# Stepper_Motor1.net
KiCad netlist of a schematic drawn in Altium Designer
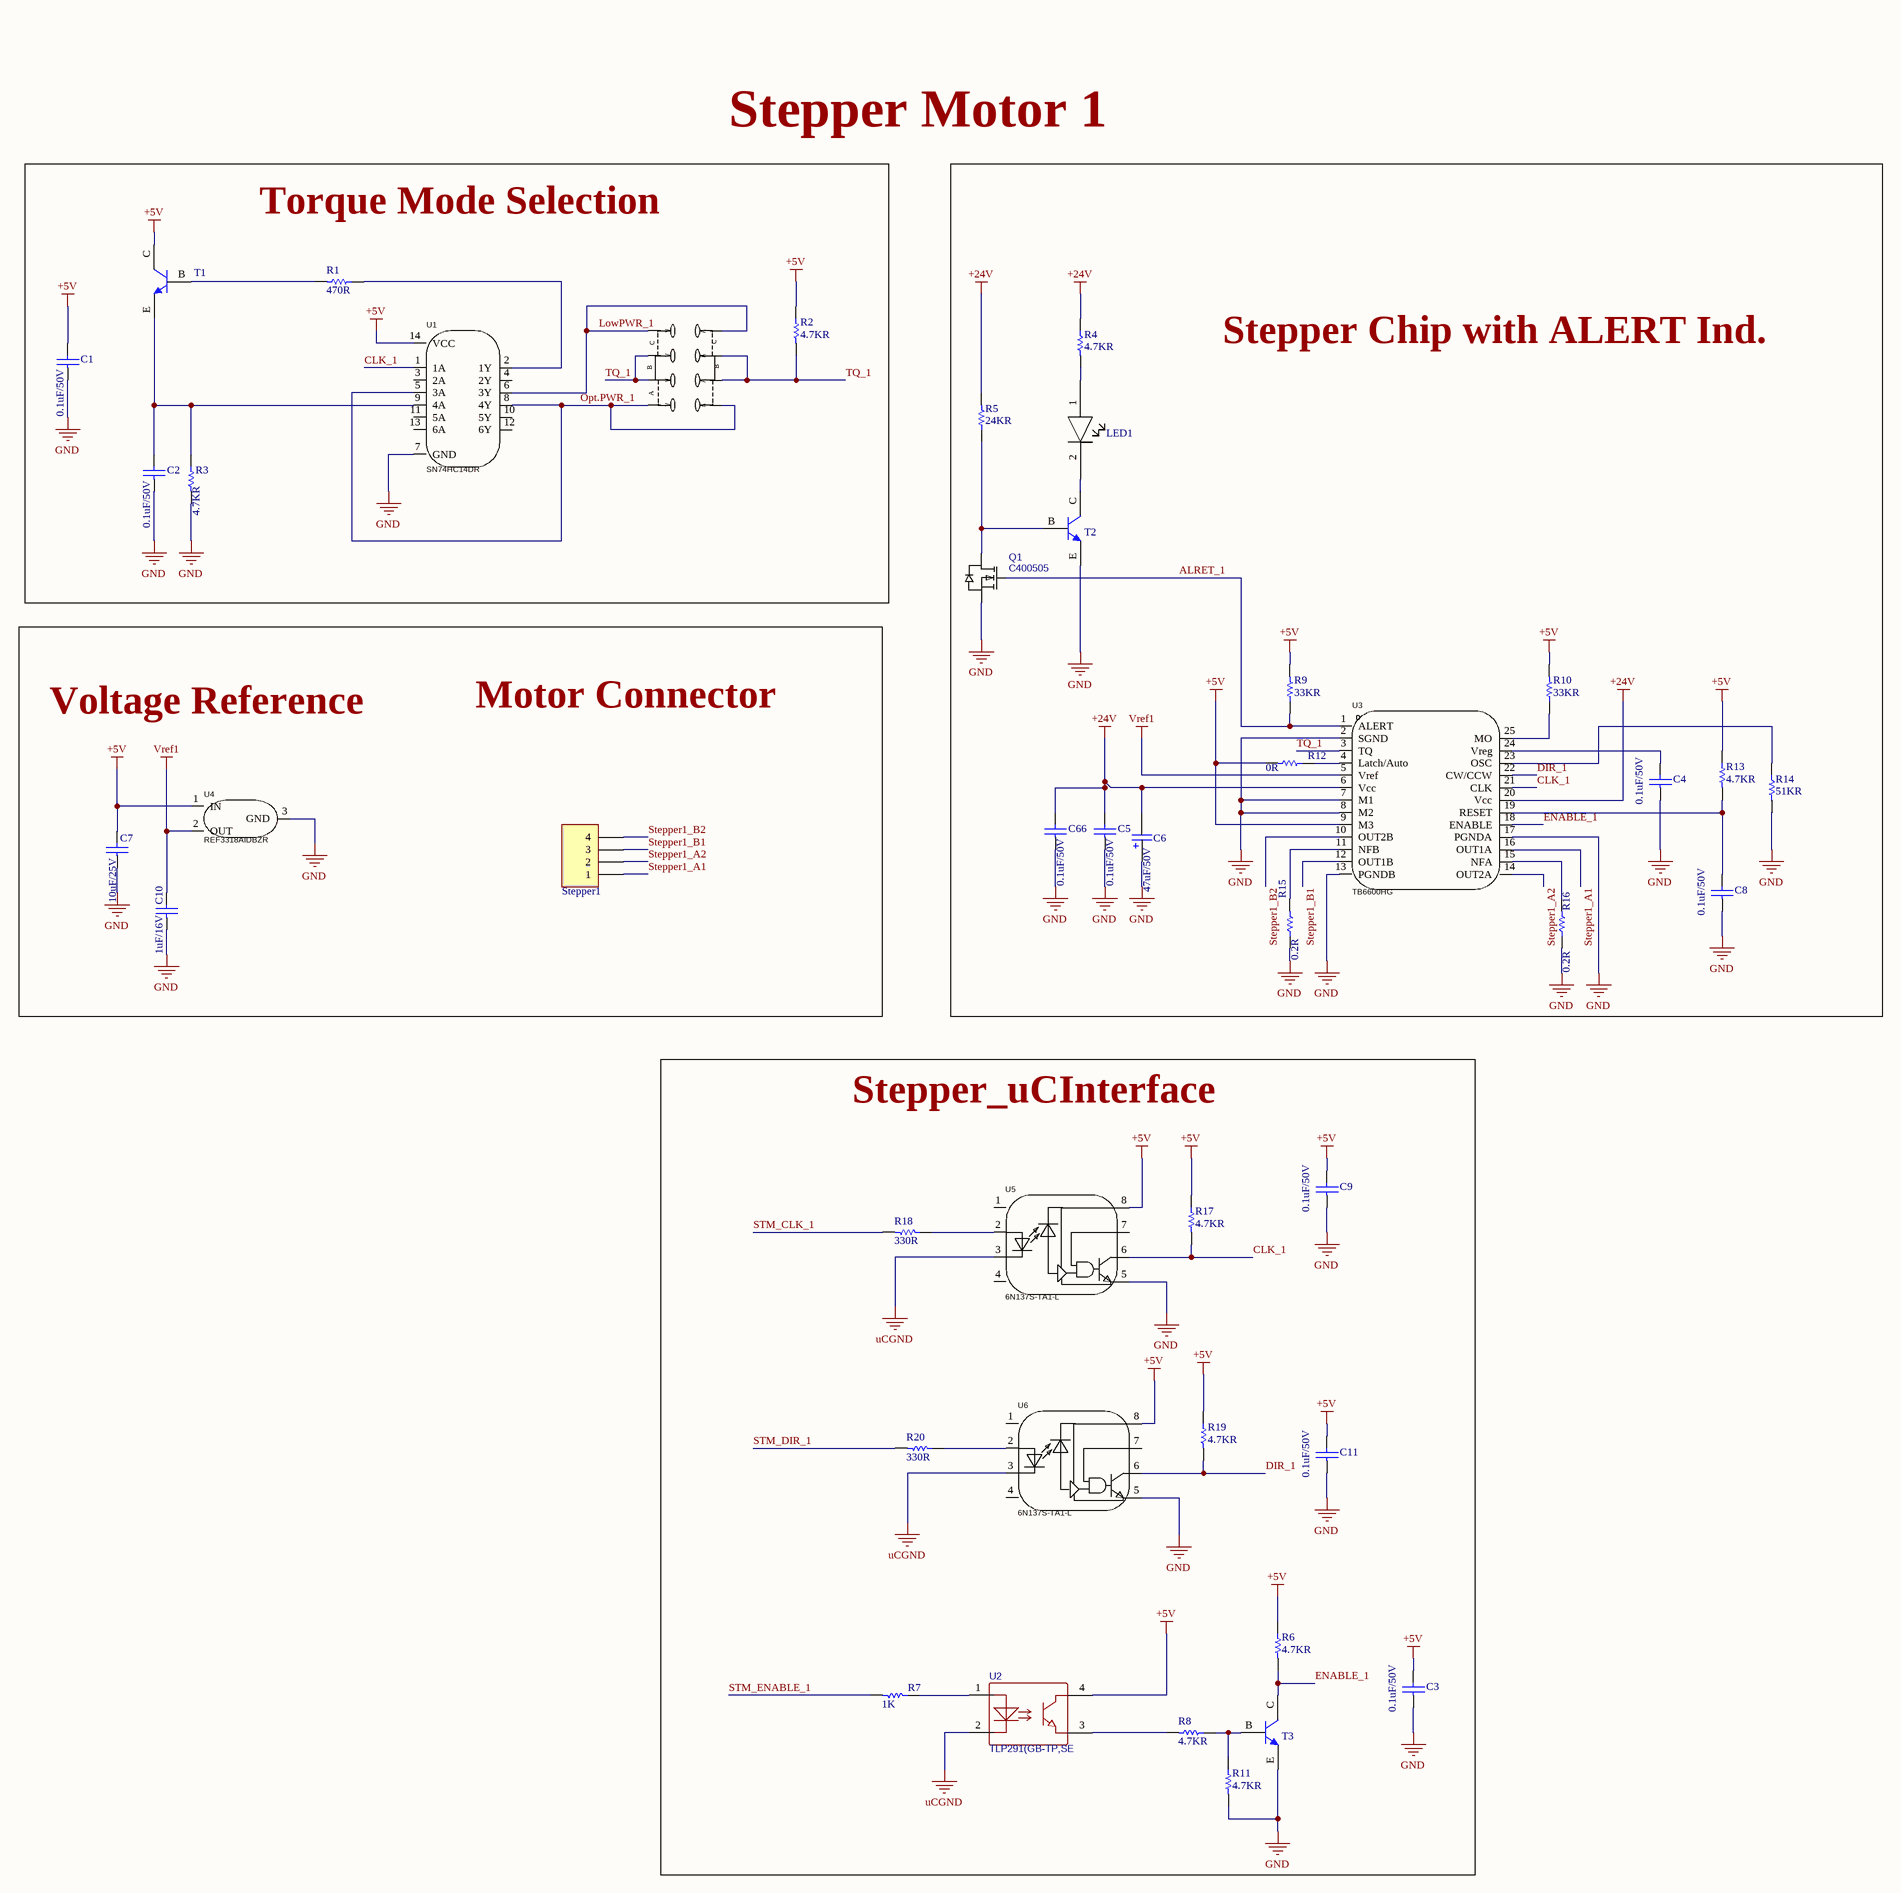
[diagram p0: Stepper Motor1.SchDoc]

(export (version "E")
  (design (tool "Eeschema 10.0.6"))
  (components
    (comp (ref "C1")
      (value "0.1uF/50V")
      (footprint "PCBComponent_1")
      (description "C1591")
      (fields (field (name "CREATED BY") "NourAldin"))
      (libsource (lib "0603 Capacitor") (part "0603 Capacitor"))
    )
    (comp (ref "C2")
      (value "0.1uF/50V")
      (footprint "PCBComponent_1")
      (description "C1591")
      (fields (field (name "CREATED BY") "NourAldin"))
      (libsource (lib "0603 Capacitor") (part "0603 Capacitor"))
    )
    (comp (ref "C3")
      (value "0.1uF/50V")
      (footprint "PCBComponent_1")
      (description "C1591")
      (fields (field (name "CREATED BY") "NourAldin"))
      (libsource (lib "0603 Capacitor") (part "0603 Capacitor"))
    )
    (comp (ref "C4")
      (value "0.1uF/50V")
      (footprint "PCBComponent_1")
      (description "C1591")
      (fields (field (name "CREATED BY") "NourAldin"))
      (libsource (lib "0603 Capacitor") (part "0603 Capacitor"))
    )
    (comp (ref "C5")
      (value "0.1uF/50V")
      (footprint "PCBComponent_1")
      (description "C1591")
      (fields (field (name "CREATED BY") "NourAldin"))
      (libsource (lib "0603 Capacitor") (part "0603 Capacitor"))
    )
    (comp (ref "C6")
      (value "47uF/50V")
      (footprint "CAPLEAD_D6.3mm")
      (description "C45100")
      (fields
        (field (name "MANUFACTURER") "KEMET")
        (field (name "MANUFACTURER PART NUMBER") "A759EQ475M2AAAE160")
      )
      (libsource (lib "GlobalLib") (part "A759EQ475M2AAAE160"))
    )
    (comp (ref "C7")
      (value "10uF/25V")
      (footprint "PCBComponent_1")
      (description "C96446")
      (fields (field (name "CREATED BY") "NourAldin"))
      (libsource (lib "0603 Capacitor") (part "0603 Capacitor"))
    )
    (comp (ref "C8")
      (value "0.1uF/50V")
      (footprint "PCBComponent_1")
      (description "C1591")
      (fields (field (name "CREATED BY") "NourAldin"))
      (libsource (lib "0603 Capacitor") (part "0603 Capacitor"))
    )
    (comp (ref "C9")
      (value "0.1uF/50V")
      (footprint "PCBComponent_1")
      (description "C1591")
      (fields (field (name "CREATED BY") "NourAldin"))
      (libsource (lib "0603 Capacitor") (part "0603 Capacitor"))
    )
    (comp (ref "C10")
      (value "1uF/16V")
      (footprint "PCBComponent_1")
      (description "C1592")
      (fields (field (name "CREATED BY") "NourAldin"))
      (libsource (lib "0603 Capacitor") (part "0603 Capacitor"))
    )
    (comp (ref "C11")
      (value "0.1uF/50V")
      (footprint "PCBComponent_1")
      (description "C1591")
      (fields (field (name "CREATED BY") "NourAldin"))
      (libsource (lib "0603 Capacitor") (part "0603 Capacitor"))
    )
    (comp (ref "C66")
      (value "0.1uF/50V")
      (footprint "PCBComponent_1")
      (description "C1591")
      (fields (field (name "CREATED BY") "NourAldin"))
      (libsource (lib "0603 Capacitor") (part "0603 Capacitor"))
    )
    (comp (ref "LED1")
      (value "1206 LED")
      (footprint "1206 LED")
      (description "C434438")
      (fields (field (name "CREATED BY") "NourAldin"))
      (libsource (lib "1206 LED") (part "1206 LED"))
    )
    (comp (ref "Q1")
      (value "C400505")
      (footprint "SOT-23-3_L2.9-W1.3-P1.90-LS2.4-BR")
      (fields
        (field (name "MANUFACTURER") "YANGJIE(扬杰)")
        (field (name "MANUFACTURER PART") "BSS138")
        (field (name "CONTRIBUTOR") "LCSC")
      )
      (libsource (lib "DIVERSE") (part "BSS138_MOSFET"))
    )
    (comp (ref "R1")
      (value "470R")
      (footprint "RESC1608X06N")
      (description "C114669")
      (fields (field (name "CREATED BY") "NourAldin"))
      (libsource (lib "0603 Resistor") (part "0603 Resistor"))
    )
    (comp (ref "R2")
      (value "4.7KR")
      (footprint "R0402")
      (description "C105871")
      (libsource (lib "DIVERSE") (part "0402 Resistor"))
    )
    (comp (ref "R3")
      (value "4.7KR")
      (footprint "R0402")
      (description "C105871")
      (libsource (lib "DIVERSE") (part "0402 Resistor"))
    )
    (comp (ref "R4")
      (value "4.7KR")
      (footprint "R0402")
      (description "C105871")
      (libsource (lib "DIVERSE") (part "0402 Resistor"))
    )
    (comp (ref "R5")
      (value "24KR")
      (footprint "RESC1608X06N")
      (description "C2930081")
      (fields (field (name "CREATED BY") "NourAldin"))
      (libsource (lib "0603 Resistor") (part "0603 Resistor"))
    )
    (comp (ref "R6")
      (value "4.7KR")
      (footprint "R0402")
      (description "C105871")
      (libsource (lib "DIVERSE") (part "0402 Resistor"))
    )
    (comp (ref "R7")
      (value "1K")
      (footprint "R0402")
      (description "C106235")
      (libsource (lib "DIVERSE") (part "0402 Resistor"))
    )
    (comp (ref "R8")
      (value "4.7KR")
      (footprint "R0402")
      (description "C105871")
      (libsource (lib "DIVERSE") (part "0402 Resistor"))
    )
    (comp (ref "R9")
      (value "33KR")
      (footprint "RESC1608X06N")
      (description "C126359")
      (fields (field (name "CREATED BY") "NourAldin"))
      (libsource (lib "0603 Resistor") (part "0603 Resistor"))
    )
    (comp (ref "R10")
      (value "33KR")
      (footprint "RESC1608X06N")
      (description "C126359")
      (fields (field (name "CREATED BY") "NourAldin"))
      (libsource (lib "0603 Resistor") (part "0603 Resistor"))
    )
    (comp (ref "R11")
      (value "4.7KR")
      (footprint "R0402")
      (description "C105871")
      (libsource (lib "DIVERSE") (part "0402 Resistor"))
    )
    (comp (ref "R12")
      (value "0R")
      (footprint "RESC1608X06N")
      (description "C100044")
      (fields (field (name "CREATED BY") "NourAldin"))
      (libsource (lib "0603 Resistor") (part "0603 Resistor"))
    )
    (comp (ref "R13")
      (value "4.7KR")
      (footprint "R0402")
      (description "C105871")
      (libsource (lib "DIVERSE") (part "0402 Resistor"))
    )
    (comp (ref "R14")
      (value "51KR")
      (footprint "R0402")
      (description "C107230")
      (libsource (lib "DIVERSE") (part "0402 Resistor"))
    )
    (comp (ref "R15")
      (value "0.2R")
      (footprint "RESC6431X12N")
      (description "C2903473")
      (fields (field (name "CREATED BY") "NourAldin"))
      (libsource (lib "2512 Resistor") (part "2512 Resistor"))
    )
    (comp (ref "R16")
      (value "0.2R")
      (footprint "RESC6431X12N")
      (description "C2903473")
      (fields (field (name "CREATED BY") "NourAldin"))
      (libsource (lib "2512 Resistor") (part "2512 Resistor"))
    )
    (comp (ref "R17")
      (value "4.7KR")
      (footprint "R0402")
      (description "C105871")
      (libsource (lib "DIVERSE") (part "0402 Resistor"))
    )
    (comp (ref "R18")
      (value "330R")
      (footprint "R0402")
      (description "C105875")
      (libsource (lib "DIVERSE") (part "0402 Resistor"))
    )
    (comp (ref "R19")
      (value "4.7KR")
      (footprint "R0402")
      (description "C105871")
      (libsource (lib "DIVERSE") (part "0402 Resistor"))
    )
    (comp (ref "R20")
      (value "330R")
      (footprint "R0402")
      (description "C105875")
      (libsource (lib "DIVERSE") (part "0402 Resistor"))
    )
    (comp (ref "Stepper1")
      (value "Header 4 Pin Polar")
      (footprint "PCBComponent_1")
      (libsource (lib "Header 4 Pin Polar") (part "Header 4 Pin Polar"))
    )
    (comp (ref "SW1")
      (value "MST23D19G2")
      (footprint "SW-SMD_MST23D19G2")
      (description "C431545")
      (fields (field (name "MANUFACTURER") "SHOU HAN(首韩)"))
      (libsource (lib "LIB") (part "MST23D19G2"))
    )
    (comp (ref "T1")
      (value "MMBT3904 Transistor")
      (footprint "MMBT3904")
      (description "C108429")
      (fields (field (name "CREATED BY") "NourAldin"))
      (libsource (lib "MMBT3904 Transistor") (part "MMBT3904 Transistor"))
    )
    (comp (ref "T2")
      (value "MMBT3904 Transistor")
      (footprint "MMBT3904")
      (description "C108429")
      (fields (field (name "CREATED BY") "NourAldin"))
      (libsource (lib "MMBT3904 Transistor") (part "MMBT3904 Transistor"))
    )
    (comp (ref "T3")
      (value "MMBT3904 Transistor")
      (footprint "MMBT3904")
      (description "C108429")
      (fields (field (name "CREATED BY") "NourAldin"))
      (libsource (lib "MMBT3904 Transistor") (part "MMBT3904 Transistor"))
    )
    (comp (ref "U1")
      (value "SN74HC14DR")
      (footprint "SOIC-14_L8.7-W3.9-P1.27-LS6.0-BL")
      (description "C6820")
      (fields (field (name "MANUFACTURER") "TI(德州仪器)"))
      (libsource (lib "LIB") (part "SN74HC14DR"))
    )
    (comp (ref "U2")
      (value "TLP291(GB-TP,SE")
      (footprint "SOP-4-1.27mm")
      (description "C55144")
      (libsource (lib "CO2_Lib") (part "TLP291(GB-TP,SE(T"))
    )
    (comp (ref "U3")
      (value "TB6600HG")
      (footprint "HZIP25-P-1.00F")
      (description "C66042")
      (fields (field (name "MANUFACTURER") "TOSHIBA(东芝)"))
      (libsource (lib "LIB") (part "TB6600HG"))
    )
    (comp (ref "U4")
      (value "REF3318AIDBZR")
      (footprint "SOT-23-3_L2.9-W1.3-P1.90-LS2.4-BR")
      (description "C115877")
      (fields (field (name "MANUFACTURER") "TI(德州仪器)") (field (name "TOLERANCE") "±0.15%"))
      (libsource (lib "LIB") (part "REF3318AIDBZR"))
    )
    (comp (ref "U5")
      (value "6N137S-TA1-L")
      (footprint "SOP-8_L9.8-W6.6-P2.54-LS10.3-BL")
      (description "C92651")
      (fields (field (name "MANUFACTURER") "LITEON(光宝)"))
      (libsource (lib "LIB") (part "6N137S-TA1-L"))
    )
    (comp (ref "U6")
      (value "6N137S-TA1-L")
      (footprint "SOP-8_L9.8-W6.6-P2.54-LS10.3-BL")
      (description "C92651")
      (fields (field (name "MANUFACTURER") "LITEON(光宝)"))
      (libsource (lib "LIB") (part "6N137S-TA1-L"))
    )
  )
  (nets
    (net (code "1") (name "+5V") (class "Default")
      (node (ref "C1") (pin "2") (pinfunction "2_2") (pintype "passive"))
      (node (ref "C11") (pin "2") (pinfunction "2_2") (pintype "passive"))
      (node (ref "C3") (pin "2") (pinfunction "2_2") (pintype "passive"))
      (node (ref "C7") (pin "2") (pinfunction "2_2") (pintype "passive"))
      (node (ref "C9") (pin "2") (pinfunction "2_2") (pintype "passive"))
      (node (ref "R10") (pin "2") (pinfunction "2_2") (pintype "passive"))
      (node (ref "R12") (pin "2") (pinfunction "2_2") (pintype "passive"))
      (node (ref "R13") (pin "1") (pinfunction "1_1") (pintype "passive"))
      (node (ref "R17") (pin "1") (pinfunction "1_1") (pintype "passive"))
      (node (ref "R19") (pin "1") (pinfunction "1_1") (pintype "passive"))
      (node (ref "R2") (pin "1") (pinfunction "1_1") (pintype "passive"))
      (node (ref "R6") (pin "1") (pinfunction "1_1") (pintype "passive"))
      (node (ref "R9") (pin "2") (pinfunction "2_2") (pintype "passive"))
      (node (ref "T1") (pin "C") (pinfunction "C_C") (pintype "passive"))
      (node (ref "U1") (pin "14") (pinfunction "VCC_14") (pintype "passive"))
      (node (ref "U2") (pin "4") (pinfunction "4_4") (pintype "passive"))
      (node (ref "U3") (pin "9") (pinfunction "M3_9") (pintype "passive"))
      (node (ref "U4") (pin "1") (pinfunction "IN_1") (pintype "passive"))
      (node (ref "U5") (pin "8") (pinfunction "8_8") (pintype "passive"))
      (node (ref "U6") (pin "8") (pinfunction "8_8") (pintype "passive"))
    )
    (net (code "2") (name "+24V") (class "Default")
      (node (ref "C5") (pin "2") (pinfunction "2_2") (pintype "passive"))
      (node (ref "C6") (pin "2") (pinfunction "2_2") (pintype "passive"))
      (node (ref "C66") (pin "2") (pinfunction "2_2") (pintype "passive"))
      (node (ref "R4") (pin "1") (pinfunction "1_1") (pintype "passive"))
      (node (ref "R5") (pin "2") (pinfunction "2_2") (pintype "passive"))
      (node (ref "U3") (pin "20") (pinfunction "Vcc_20") (pintype "passive"))
      (node (ref "U3") (pin "6") (pinfunction "Vcc_6") (pintype "passive"))
    )
    (net (code "3") (name "/ALRET_1") (class "Default")
      (node (ref "Q1") (pin "1") (pinfunction "G_1") (pintype "passive"))
      (node (ref "R9") (pin "1") (pinfunction "1_1") (pintype "passive"))
      (node (ref "U3") (pin "1") (pinfunction "ALERT_1") (pintype "passive"))
    )
    (net (code "4") (name "/CLK_1") (class "Default")
      (node (ref "R17") (pin "2") (pinfunction "2_2") (pintype "passive"))
      (node (ref "U1") (pin "1") (pinfunction "1A_1") (pintype "passive"))
      (node (ref "U3") (pin "21") (pinfunction "CLK_21") (pintype "passive"))
      (node (ref "U5") (pin "6") (pinfunction "6_6") (pintype "passive"))
    )
    (net (code "5") (name "/DIR_1") (class "Default")
      (node (ref "R19") (pin "2") (pinfunction "2_2") (pintype "passive"))
      (node (ref "U3") (pin "22") (pinfunction "CW/CCW_22") (pintype "passive"))
      (node (ref "U6") (pin "6") (pinfunction "6_6") (pintype "passive"))
    )
    (net (code "6") (name "/ENABLE_1") (class "Default")
      (node (ref "R6") (pin "2") (pinfunction "2_2") (pintype "passive"))
      (node (ref "T3") (pin "C") (pinfunction "C_C") (pintype "passive"))
      (node (ref "U3") (pin "18") (pinfunction "ENABLE_18") (pintype "passive"))
    )
    (net (code "7") (name "/LowPWR_1") (class "Default")
      (node (ref "SW1") (pin "4") (pinfunction "4_4") (pintype "passive"))
      (node (ref "SW1") (pin "5") (pinfunction "5_5") (pintype "passive"))
      (node (ref "U1") (pin "6") (pinfunction "3Y_6") (pintype "passive"))
    )
    (net (code "8") (name "/Opt.PWR_1") (class "Default")
      (node (ref "SW1") (pin "1") (pinfunction "1_1") (pintype "passive"))
      (node (ref "SW1") (pin "8") (pinfunction "8_8") (pintype "passive"))
      (node (ref "U1") (pin "5") (pinfunction "3A_5") (pintype "passive"))
      (node (ref "U1") (pin "8") (pinfunction "4Y_8") (pintype "passive"))
    )
    (net (code "9") (name "/STM_CLK_1") (class "Default")
      (node (ref "R18") (pin "2") (pinfunction "2_2") (pintype "passive"))
    )
    (net (code "10") (name "/STM_DIR_1") (class "Default")
      (node (ref "R20") (pin "2") (pinfunction "2_2") (pintype "passive"))
    )
    (net (code "11") (name "/STM_ENABLE_1") (class "Default")
      (node (ref "R7") (pin "2") (pinfunction "2_2") (pintype "passive"))
    )
    (net (code "12") (name "/Stepper1_A1") (class "Default")
      (node (ref "Stepper1") (pin "1") (pinfunction "1_1") (pintype "passive"))
      (node (ref "U3") (pin "16") (pinfunction "OUT1A_16") (pintype "passive"))
    )
    (net (code "13") (name "/Stepper1_A2") (class "Default")
      (node (ref "Stepper1") (pin "2") (pinfunction "2_2") (pintype "passive"))
      (node (ref "U3") (pin "14") (pinfunction "OUT2A_14") (pintype "passive"))
    )
    (net (code "14") (name "/Stepper1_B1") (class "Default")
      (node (ref "Stepper1") (pin "3") (pinfunction "3_3") (pintype "passive"))
      (node (ref "U3") (pin "12") (pinfunction "OUT1B_12") (pintype "passive"))
    )
    (net (code "15") (name "/Stepper1_B2") (class "Default")
      (node (ref "Stepper1") (pin "4") (pinfunction "4_4") (pintype "passive"))
      (node (ref "U3") (pin "10") (pinfunction "OUT2B_10") (pintype "passive"))
    )
    (net (code "16") (name "/TQ_1") (class "Default")
      (node (ref "R2") (pin "2") (pinfunction "2_2") (pintype "passive"))
      (node (ref "SW1") (pin "2") (pinfunction "2_2") (pintype "passive"))
      (node (ref "SW1") (pin "3") (pinfunction "3_3") (pintype "passive"))
      (node (ref "SW1") (pin "6") (pinfunction "6_6") (pintype "passive"))
      (node (ref "SW1") (pin "7") (pinfunction "7_7") (pintype "passive"))
      (node (ref "U3") (pin "3") (pinfunction "TQ_3") (pintype "passive"))
    )
    (net (code "17") (name "GND") (class "Default")
      (node (ref "C1") (pin "1") (pinfunction "1_1") (pintype "passive"))
      (node (ref "C10") (pin "1") (pinfunction "1_1") (pintype "passive"))
      (node (ref "C11") (pin "1") (pinfunction "1_1") (pintype "passive"))
      (node (ref "C2") (pin "1") (pinfunction "1_1") (pintype "passive"))
      (node (ref "C3") (pin "1") (pinfunction "1_1") (pintype "passive"))
      (node (ref "C4") (pin "1") (pinfunction "1_1") (pintype "passive"))
      (node (ref "C5") (pin "1") (pinfunction "1_1") (pintype "passive"))
      (node (ref "C6") (pin "1") (pinfunction "1_1") (pintype "passive"))
      (node (ref "C66") (pin "1") (pinfunction "1_1") (pintype "passive"))
      (node (ref "C7") (pin "1") (pinfunction "1_1") (pintype "passive"))
      (node (ref "C8") (pin "1") (pinfunction "1_1") (pintype "passive"))
      (node (ref "C9") (pin "1") (pinfunction "1_1") (pintype "passive"))
      (node (ref "Q1") (pin "2") (pinfunction "S_2") (pintype "passive"))
      (node (ref "R11") (pin "2") (pinfunction "2_2") (pintype "passive"))
      (node (ref "R14") (pin "2") (pinfunction "2_2") (pintype "passive"))
      (node (ref "R15") (pin "1") (pinfunction "1_1") (pintype "passive"))
      (node (ref "R16") (pin "1") (pinfunction "1_1") (pintype "passive"))
      (node (ref "R3") (pin "2") (pinfunction "2_2") (pintype "passive"))
      (node (ref "T2") (pin "E") (pinfunction "E_E") (pintype "passive"))
      (node (ref "T3") (pin "E") (pinfunction "E_E") (pintype "passive"))
      (node (ref "U1") (pin "7") (pinfunction "GND_7") (pintype "passive"))
      (node (ref "U3") (pin "13") (pinfunction "PGNDB_13") (pintype "passive"))
      (node (ref "U3") (pin "17") (pinfunction "PGNDA_17") (pintype "passive"))
      (node (ref "U3") (pin "2") (pinfunction "SGND_2") (pintype "passive"))
      (node (ref "U3") (pin "7") (pinfunction "M1_7") (pintype "passive"))
      (node (ref "U3") (pin "8") (pinfunction "M2_8") (pintype "passive"))
      (node (ref "U4") (pin "3") (pinfunction "GND_3") (pintype "passive"))
      (node (ref "U5") (pin "5") (pinfunction "5_5") (pintype "passive"))
      (node (ref "U6") (pin "5") (pinfunction "5_5") (pintype "passive"))
    )
    (net (code "18") (name "Net-(LED1-Pad1)") (class "Default")
      (node (ref "LED1") (pin "1") (pinfunction "1_1") (pintype "passive"))
      (node (ref "R4") (pin "2") (pinfunction "2_2") (pintype "passive"))
    )
    (net (code "19") (name "Net-(LED1-Pad2)") (class "Default")
      (node (ref "LED1") (pin "2") (pinfunction "2_2") (pintype "passive"))
      (node (ref "T2") (pin "C") (pinfunction "C_C") (pintype "passive"))
    )
    (net (code "20") (name "Net-(Q1-D)") (class "Default")
      (node (ref "Q1") (pin "3") (pinfunction "D_3") (pintype "passive"))
      (node (ref "R5") (pin "1") (pinfunction "1_1") (pintype "passive"))
      (node (ref "T2") (pin "B") (pinfunction "B_B") (pintype "passive"))
    )
    (net (code "21") (name "Net-(R1-Pad2)") (class "Default")
      (node (ref "R1") (pin "2") (pinfunction "2_2") (pintype "passive"))
      (node (ref "T1") (pin "B") (pinfunction "B_B") (pintype "passive"))
    )
    (net (code "22") (name "Net-(R7-Pad1)") (class "Default")
      (node (ref "R7") (pin "1") (pinfunction "1_1") (pintype "passive"))
      (node (ref "U2") (pin "1") (pinfunction "1_1") (pintype "passive"))
    )
    (net (code "23") (name "Net-(R8-Pad2)") (class "Default")
      (node (ref "R8") (pin "2") (pinfunction "2_2") (pintype "passive"))
      (node (ref "U2") (pin "3") (pinfunction "3_3") (pintype "passive"))
    )
    (net (code "24") (name "Net-(R11-Pad1)") (class "Default")
      (node (ref "R11") (pin "1") (pinfunction "1_1") (pintype "passive"))
      (node (ref "R8") (pin "1") (pinfunction "1_1") (pintype "passive"))
      (node (ref "T3") (pin "B") (pinfunction "B_B") (pintype "passive"))
    )
    (net (code "25") (name "Net-(R18-Pad1)") (class "Default")
      (node (ref "R18") (pin "1") (pinfunction "1_1") (pintype "passive"))
      (node (ref "U5") (pin "2") (pinfunction "2_2") (pintype "passive"))
    )
    (net (code "26") (name "Net-(R20-Pad1)") (class "Default")
      (node (ref "R20") (pin "1") (pinfunction "1_1") (pintype "passive"))
      (node (ref "U6") (pin "2") (pinfunction "2_2") (pintype "passive"))
    )
    (net (code "27") (name "Net-(U1-1Y)") (class "Default")
      (node (ref "R1") (pin "1") (pinfunction "1_1") (pintype "passive"))
      (node (ref "U1") (pin "2") (pinfunction "1Y_2") (pintype "passive"))
    )
    (net (code "28") (name "Net-(U1-4A)") (class "Default")
      (node (ref "C2") (pin "2") (pinfunction "2_2") (pintype "passive"))
      (node (ref "R3") (pin "1") (pinfunction "1_1") (pintype "passive"))
      (node (ref "T1") (pin "E") (pinfunction "E_E") (pintype "passive"))
      (node (ref "U1") (pin "9") (pinfunction "4A_9") (pintype "passive"))
    )
    (net (code "29") (name "Net-(U3-Latch{slash}Auto)") (class "Default")
      (node (ref "R12") (pin "1") (pinfunction "1_1") (pintype "passive"))
      (node (ref "U3") (pin "4") (pinfunction "Latch/Auto_4") (pintype "passive"))
    )
    (net (code "30") (name "Net-(U3-MO)") (class "Default")
      (node (ref "R10") (pin "1") (pinfunction "1_1") (pintype "passive"))
      (node (ref "U3") (pin "25") (pinfunction "MO_25") (pintype "passive"))
    )
    (net (code "31") (name "Net-(U3-NFA)") (class "Default")
      (node (ref "R16") (pin "2") (pinfunction "2_2") (pintype "passive"))
      (node (ref "U3") (pin "15") (pinfunction "NFA_15") (pintype "passive"))
    )
    (net (code "32") (name "Net-(U3-NFB)") (class "Default")
      (node (ref "R15") (pin "2") (pinfunction "2_2") (pintype "passive"))
      (node (ref "U3") (pin "11") (pinfunction "NFB_11") (pintype "passive"))
    )
    (net (code "33") (name "Net-(U3-OSC)") (class "Default")
      (node (ref "R14") (pin "1") (pinfunction "1_1") (pintype "passive"))
      (node (ref "U3") (pin "23") (pinfunction "OSC_23") (pintype "passive"))
    )
    (net (code "34") (name "Net-(U3-RESET)") (class "Default")
      (node (ref "C8") (pin "2") (pinfunction "2_2") (pintype "passive"))
      (node (ref "R13") (pin "2") (pinfunction "2_2") (pintype "passive"))
      (node (ref "U3") (pin "19") (pinfunction "RESET_19") (pintype "passive"))
    )
    (net (code "35") (name "Net-(U3-Vreg)") (class "Default")
      (node (ref "C4") (pin "2") (pinfunction "2_2") (pintype "passive"))
      (node (ref "U3") (pin "24") (pinfunction "Vreg_24") (pintype "passive"))
    )
    (net (code "36") (name "Vref1") (class "Default")
      (node (ref "C10") (pin "2") (pinfunction "2_2") (pintype "passive"))
      (node (ref "U3") (pin "5") (pinfunction "Vref_5") (pintype "passive"))
      (node (ref "U4") (pin "2") (pinfunction "OUT_2") (pintype "passive"))
    )
    (net (code "37") (name "uCGND") (class "Default")
      (node (ref "U2") (pin "2") (pinfunction "2_2") (pintype "passive"))
      (node (ref "U5") (pin "3") (pinfunction "3_3") (pintype "passive"))
      (node (ref "U6") (pin "3") (pinfunction "3_3") (pintype "passive"))
    )
    (net (code "38") (name "unconnected-(U1-2A-Pad3)") (class "Default")
      (node (ref "U1") (pin "3") (pinfunction "2A_3") (pintype "passive"))
    )
    (net (code "39") (name "unconnected-(U1-2Y-Pad4)") (class "Default")
      (node (ref "U1") (pin "4") (pinfunction "2Y_4") (pintype "passive"))
    )
    (net (code "40") (name "unconnected-(U1-5A-Pad11)") (class "Default")
      (node (ref "U1") (pin "11") (pinfunction "5A_11") (pintype "passive"))
    )
    (net (code "41") (name "unconnected-(U1-5Y-Pad10)") (class "Default")
      (node (ref "U1") (pin "10") (pinfunction "5Y_10") (pintype "passive"))
    )
    (net (code "42") (name "unconnected-(U1-6A-Pad13)") (class "Default")
      (node (ref "U1") (pin "13") (pinfunction "6A_13") (pintype "passive"))
    )
    (net (code "43") (name "unconnected-(U1-6Y-Pad12)") (class "Default")
      (node (ref "U1") (pin "12") (pinfunction "6Y_12") (pintype "passive"))
    )
    (net (code "44") (name "unconnected-(U5-NC-Pad1)") (class "Default")
      (node (ref "U5") (pin "1") (pinfunction "NC_1") (pintype "passive"))
    )
    (net (code "45") (name "unconnected-(U5-NC-Pad4)") (class "Default")
      (node (ref "U5") (pin "4") (pinfunction "NC_4") (pintype "passive"))
    )
    (net (code "46") (name "unconnected-(U5-Pad7)") (class "Default")
      (node (ref "U5") (pin "7") (pinfunction "7_7") (pintype "passive"))
    )
    (net (code "47") (name "unconnected-(U6-NC-Pad1)") (class "Default")
      (node (ref "U6") (pin "1") (pinfunction "NC_1") (pintype "passive"))
    )
    (net (code "48") (name "unconnected-(U6-NC-Pad4)") (class "Default")
      (node (ref "U6") (pin "4") (pinfunction "NC_4") (pintype "passive"))
    )
    (net (code "49") (name "unconnected-(U6-Pad7)") (class "Default")
      (node (ref "U6") (pin "7") (pinfunction "7_7") (pintype "passive"))
    )
  )
)
